# IMU_BMI270.net
KiCad netlist of a schematic drawn in Altium Designer
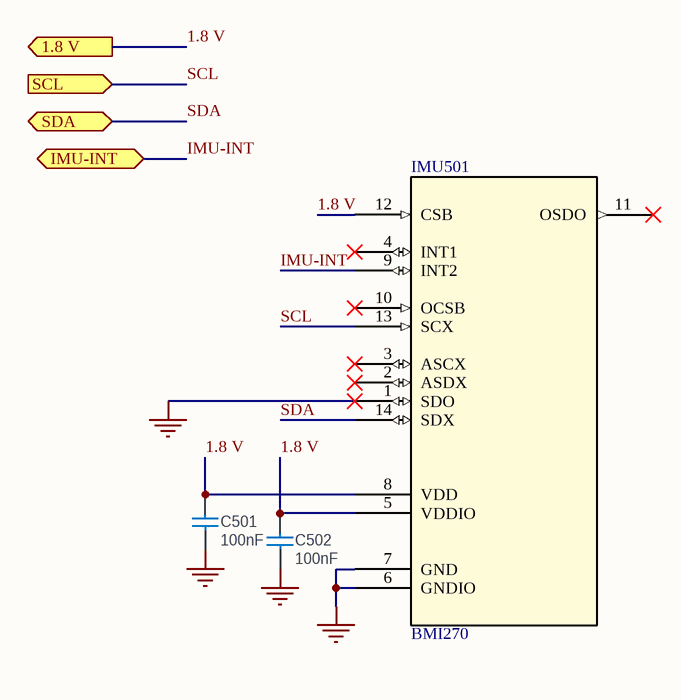
[diagram p0: IMU (BMI270).SchDoc]

(export (version "E")
  (design (tool "Eeschema 10.0.6"))
  (components
    (comp (ref "C501")
      (value "100nF")
      (footprint "CAPC0603X03L_C")
      (description "Capacitor, X7S, ±10%")
      (fields (field (name "AUTHOR") "rsk"))
      (libsource (lib "Watch_Components") (part "C0201-100n-16V-X7S"))
    )
    (comp (ref "C502")
      (value "100nF")
      (footprint "CAPC0603X03L_C")
      (description "Capacitor, X7S, ±10%")
      (fields (field (name "AUTHOR") "rsk"))
      (libsource (lib "Watch_Components") (part "C0201-100n-16V-X7S"))
    )
    (comp (ref "IMU501")
      (value "BMI270")
      (footprint "BMI270_BOS")
      (description "Inertial Measurement Unit Digital Output 1.8V/2.5V/3.3V Automotive 14-Pin LGA")
      (fields (field (name "MANUFACTURER") "Bosch Tools"))
      (libsource (lib "Watch_Components") (part "BMI270"))
    )
  )
  (nets
    (net (code "1") (name "/1.8 V") (class "Default")
      (node (ref "C501") (pin "2") (pinfunction "2_2") (pintype "passive"))
      (node (ref "C502") (pin "2") (pinfunction "2_2") (pintype "passive"))
      (node (ref "IMU501") (pin "12") (pinfunction "CSB_12") (pintype "input"))
      (node (ref "IMU501") (pin "5") (pinfunction "VDDIO_5") (pintype "passive"))
      (node (ref "IMU501") (pin "8") (pinfunction "VDD_8") (pintype "passive"))
    )
    (net (code "2") (name "/IMU-INT") (class "Default")
      (node (ref "IMU501") (pin "9") (pinfunction "INT2_9") (pintype "bidirectional"))
    )
    (net (code "3") (name "/SCL") (class "Default")
      (node (ref "IMU501") (pin "13") (pinfunction "SCX_13") (pintype "input"))
    )
    (net (code "4") (name "/SDA") (class "Default")
      (node (ref "IMU501") (pin "14") (pinfunction "SDX_14") (pintype "bidirectional"))
    )
    (net (code "5") (name "GND") (class "Default")
      (node (ref "C501") (pin "1") (pinfunction "1_1") (pintype "passive"))
      (node (ref "C502") (pin "1") (pinfunction "1_1") (pintype "passive"))
      (node (ref "IMU501") (pin "1") (pinfunction "SDO_1") (pintype "bidirectional"))
      (node (ref "IMU501") (pin "6") (pinfunction "GNDIO_6") (pintype "passive"))
      (node (ref "IMU501") (pin "7") (pinfunction "GND_7") (pintype "passive"))
    )
    (net (code "6") (name "unconnected-(IMU501-ASCX-Pad3)") (class "Default")
      (node (ref "IMU501") (pin "3") (pinfunction "ASCX_3") (pintype "bidirectional+no_connect"))
    )
    (net (code "7") (name "unconnected-(IMU501-ASDX-Pad2)") (class "Default")
      (node (ref "IMU501") (pin "2") (pinfunction "ASDX_2") (pintype "bidirectional+no_connect"))
    )
    (net (code "8") (name "unconnected-(IMU501-INT1-Pad4)") (class "Default")
      (node (ref "IMU501") (pin "4") (pinfunction "INT1_4") (pintype "bidirectional+no_connect"))
    )
    (net (code "9") (name "unconnected-(IMU501-OCSB-Pad10)") (class "Default")
      (node (ref "IMU501") (pin "10") (pinfunction "OCSB_10") (pintype "input+no_connect"))
    )
    (net (code "10") (name "unconnected-(IMU501-OSDO-Pad11)") (class "Default")
      (node (ref "IMU501") (pin "11") (pinfunction "OSDO_11") (pintype "output+no_connect"))
    )
  )
)
